# Mainboard_User_Interface.net
KiCad netlist of a schematic drawn in Altium Designer
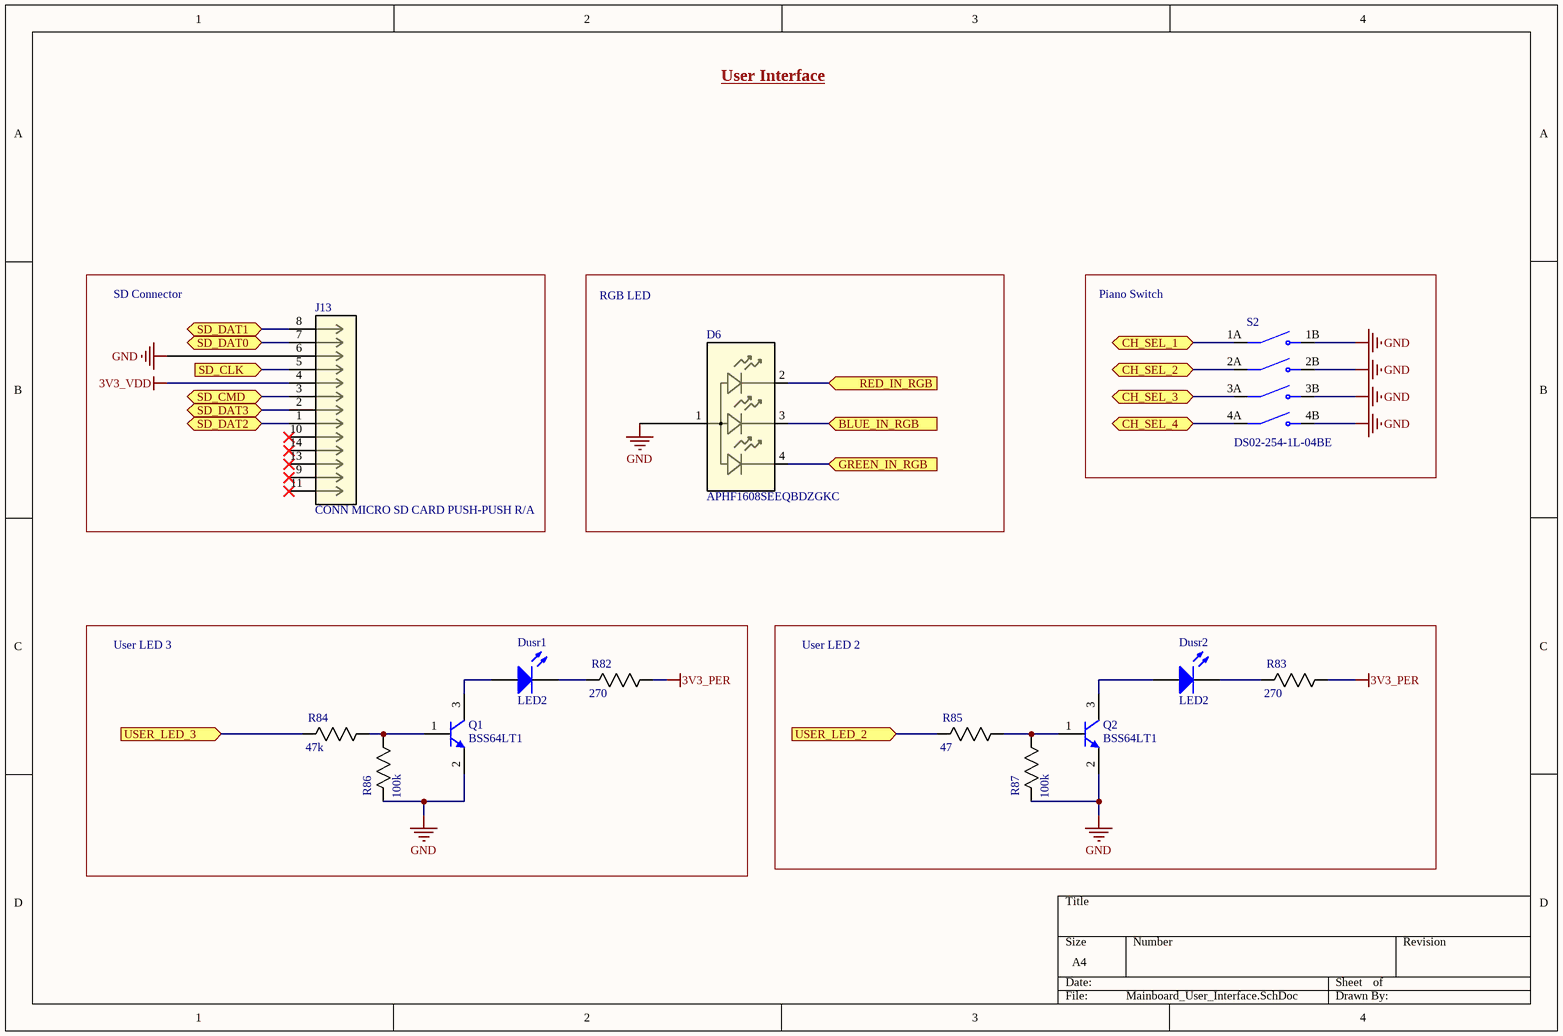
[diagram p0: Mainboard_User_Interface.SchDoc]

(export (version "E")
  (design (tool "Eeschema 10.0.6"))
  (components
    (comp (ref "D6")
      (value "APHF1608SEEQBDZGKC")
      (footprint "LED RGB APHF1608SEEQBDZGKC_KNB-L")
      (fields (field (name "MF") "Kingbright"))
      (libsource (lib "AltiumLibraries") (part "LED RGB CLEAR 4SMD"))
    )
    (comp (ref "Dusr1")
      (value "LED2")
      (footprint "3.2X1.6X1.1")
      (description "Typical RED, GREEN, YELLOW, AMBER GaAs LED")
      (libsource (lib "AltiumLibraries") (part "LED RED SMD"))
    )
    (comp (ref "Dusr2")
      (value "LED2")
      (footprint "3.2X1.6X1.1")
      (description "Typical RED, GREEN, YELLOW, AMBER GaAs LED")
      (libsource (lib "AltiumLibraries") (part "LED GREEN SMD"))
    )
    (comp (ref "J13")
      (value "CONN MICRO SD CARD PUSH-PUSH R/A")
      (footprint "SD Connector 5027740891")
      (description "10 (8 + 2) Position Card Connector Secure Digital - microSD™ Surface Mount, Right Angle Gold")
      (fields (field (name "MF") "Molex") (field (name "MP") "5027740891"))
      (libsource (lib "AltiumLibraries") (part "CONN MICRO SD CARD PUSH-PUSH R/A"))
    )
    (comp (ref "Q1")
      (value "BSS64LT1")
      (footprint "ONSC-SOT-23-3-318-08_V")
      (description "Driver Transistor, NPN Silicon, 3-Pin SOT-23, Tape and Reel")
      (fields (field (name "MANUFACTURER") "On Semiconductor"))
      (libsource (lib "Altium Content Vault") (part "ONSC-NPN-B1E2C3-3"))
    )
    (comp (ref "Q2")
      (value "BSS64LT1")
      (footprint "ONSC-SOT-23-3-318-08_V")
      (description "Driver Transistor, NPN Silicon, 3-Pin SOT-23, Tape and Reel")
      (fields (field (name "MANUFACTURER") "On Semiconductor"))
      (libsource (lib "Altium Content Vault") (part "ONSC-NPN-B1E2C3-3"))
    )
    (comp (ref "R82")
      (value "270")
      (footprint "0805")
      (description "RES SMD 270 OHM 5% 1/8W 0805")
      (fields (field (name "TOLERANCE") "5%"))
      (libsource (lib "AltiumLibraries") (part "RES 270.0 1/8W"))
    )
    (comp (ref "R83")
      (value "270")
      (footprint "0805")
      (description "RES SMD 270 OHM 5% 1/8W 0805")
      (fields (field (name "TOLERANCE") "5%"))
      (libsource (lib "AltiumLibraries") (part "RES 270.0 1/8W"))
    )
    (comp (ref "R84")
      (value "47k")
      (footprint "0805")
      (description "RES SMD 47K OHM 1% 1/8W 0805")
      (fields (field (name "TOLERANCE") "1%"))
      (libsource (lib "AltiumLibraries") (part "RES 47k 1/8W - 1%"))
    )
    (comp (ref "R85")
      (value "47")
      (footprint "0805")
      (description "RES SMD 47 OHM 1% 1/8W 0805")
      (fields (field (name "TOLERANCE") "1%"))
      (libsource (lib "AltiumLibraries") (part "RES 47.0 1/8W - 1%"))
    )
    (comp (ref "R86")
      (value "100k")
      (footprint "0805")
      (description "RES SMD 100K OHM 1% 1/8W 0805")
      (fields (field (name "TOLERANCE") "1%"))
      (libsource (lib "AltiumLibraries") (part "RES 100k 1/8W - 1%"))
    )
    (comp (ref "R87")
      (value "100k")
      (footprint "0805")
      (description "RES SMD 100K OHM 1% 1/8W 0805")
      (fields (field (name "TOLERANCE") "1%"))
      (libsource (lib "AltiumLibraries") (part "RES 100k 1/8W - 1%"))
    )
    (comp (ref "S2")
      (value "DS02-254-1L-04BE")
      (footprint "SW_DS02-254-1L-04BE")
      (description "Dip Switch Piano Key 4-position")
      (libsource (lib "AltiumLibraries") (part "DS02-254-1L-04BE"))
    )
  )
  (nets
    (net (code "1") (name "/BLUE_IN_RGB") (class "Default")
      (node (ref "D6") (pin "3") (pinfunction "3_3") (pintype "passive"))
    )
    (net (code "2") (name "/CH_SEL_1") (class "Default")
      (node (ref "S2") (pin "1A") (pinfunction "COM1_1A") (pintype "passive"))
    )
    (net (code "3") (name "/CH_SEL_2") (class "Default")
      (node (ref "S2") (pin "2A") (pinfunction "COM2_2A") (pintype "passive"))
    )
    (net (code "4") (name "/CH_SEL_3") (class "Default")
      (node (ref "S2") (pin "3A") (pinfunction "COM3_3A") (pintype "passive"))
    )
    (net (code "5") (name "/CH_SEL_4") (class "Default")
      (node (ref "S2") (pin "4A") (pinfunction "COM4_4A") (pintype "passive"))
    )
    (net (code "6") (name "/GREEN_IN_RGB") (class "Default")
      (node (ref "D6") (pin "4") (pinfunction "4_4") (pintype "passive"))
    )
    (net (code "7") (name "/RED_IN_RGB") (class "Default")
      (node (ref "D6") (pin "2") (pinfunction "2_2") (pintype "passive"))
    )
    (net (code "8") (name "/SD_CLK") (class "Default")
      (node (ref "J13") (pin "5") (pinfunction "5_5") (pintype "passive"))
    )
    (net (code "9") (name "/SD_CMD") (class "Default")
      (node (ref "J13") (pin "3") (pinfunction "3_3") (pintype "passive"))
    )
    (net (code "10") (name "/SD_DAT0") (class "Default")
      (node (ref "J13") (pin "7") (pinfunction "7_7") (pintype "passive"))
    )
    (net (code "11") (name "/SD_DAT1") (class "Default")
      (node (ref "J13") (pin "8") (pinfunction "8_8") (pintype "passive"))
    )
    (net (code "12") (name "/SD_DAT2") (class "Default")
      (node (ref "J13") (pin "1") (pinfunction "1_1") (pintype "passive"))
    )
    (net (code "13") (name "/SD_DAT3") (class "Default")
      (node (ref "J13") (pin "2") (pinfunction "2_2") (pintype "passive"))
    )
    (net (code "14") (name "/USER_LED_2") (class "Default")
      (node (ref "R85") (pin "2") (pinfunction "R2_2") (pintype "passive"))
    )
    (net (code "15") (name "/USER_LED_3") (class "Default")
      (node (ref "R84") (pin "2") (pinfunction "R2_2") (pintype "passive"))
    )
    (net (code "16") (name "3V3_PER") (class "Default")
      (node (ref "R82") (pin "1") (pinfunction "R1_1") (pintype "passive"))
      (node (ref "R83") (pin "1") (pinfunction "R1_1") (pintype "passive"))
    )
    (net (code "17") (name "3V3_VDD") (class "Default")
      (node (ref "J13") (pin "4") (pinfunction "4_4") (pintype "passive"))
    )
    (net (code "18") (name "GND") (class "Default")
      (node (ref "D6") (pin "1") (pinfunction "1_1") (pintype "passive"))
      (node (ref "J13") (pin "6") (pinfunction "6_6") (pintype "passive"))
      (node (ref "Q1") (pin "2") (pinfunction "E_2") (pintype "passive"))
      (node (ref "Q2") (pin "2") (pinfunction "E_2") (pintype "passive"))
      (node (ref "R86") (pin "2") (pinfunction "R2_2") (pintype "passive"))
      (node (ref "R87") (pin "2") (pinfunction "R2_2") (pintype "passive"))
      (node (ref "S2") (pin "1B") (pinfunction "NO1_1B") (pintype "passive"))
      (node (ref "S2") (pin "2B") (pinfunction "NO2_2B") (pintype "passive"))
      (node (ref "S2") (pin "3B") (pinfunction "NO3_3B") (pintype "passive"))
      (node (ref "S2") (pin "4B") (pinfunction "NO4_4B") (pintype "passive"))
    )
    (net (code "19") (name "Net-(Dusr1-A)") (class "Default")
      (node (ref "Dusr1") (pin "1") (pinfunction "A_1") (pintype "passive"))
      (node (ref "Q1") (pin "3") (pinfunction "C_3") (pintype "passive"))
    )
    (net (code "20") (name "Net-(Dusr1-K)") (class "Default")
      (node (ref "Dusr1") (pin "2") (pinfunction "K_2") (pintype "passive"))
      (node (ref "R82") (pin "2") (pinfunction "R2_2") (pintype "passive"))
    )
    (net (code "21") (name "Net-(Dusr2-A)") (class "Default")
      (node (ref "Dusr2") (pin "1") (pinfunction "A_1") (pintype "passive"))
      (node (ref "Q2") (pin "3") (pinfunction "C_3") (pintype "passive"))
    )
    (net (code "22") (name "Net-(Dusr2-K)") (class "Default")
      (node (ref "Dusr2") (pin "2") (pinfunction "K_2") (pintype "passive"))
      (node (ref "R83") (pin "2") (pinfunction "R2_2") (pintype "passive"))
    )
    (net (code "23") (name "Net-(Q1-B)") (class "Default")
      (node (ref "Q1") (pin "1") (pinfunction "B_1") (pintype "passive"))
      (node (ref "R84") (pin "1") (pinfunction "R1_1") (pintype "passive"))
      (node (ref "R86") (pin "1") (pinfunction "R1_1") (pintype "passive"))
    )
    (net (code "24") (name "Net-(Q2-B)") (class "Default")
      (node (ref "Q2") (pin "1") (pinfunction "B_1") (pintype "passive"))
      (node (ref "R85") (pin "1") (pinfunction "R1_1") (pintype "passive"))
      (node (ref "R87") (pin "1") (pinfunction "R1_1") (pintype "passive"))
    )
    (net (code "25") (name "unconnected-(J13-Pad9)") (class "Default")
      (node (ref "J13") (pin "9") (pinfunction "9_9") (pintype "passive+no_connect"))
    )
    (net (code "26") (name "unconnected-(J13-Pad10)") (class "Default")
      (node (ref "J13") (pin "10") (pinfunction "10_10") (pintype "passive+no_connect"))
    )
    (net (code "27") (name "unconnected-(J13-Pad11)") (class "Default")
      (node (ref "J13") (pin "11") (pinfunction "11_11") (pintype "passive+no_connect"))
    )
    (net (code "28") (name "unconnected-(J13-Pad13)") (class "Default")
      (node (ref "J13") (pin "13") (pinfunction "13_13") (pintype "passive+no_connect"))
    )
    (net (code "29") (name "unconnected-(J13-Pad14)") (class "Default")
      (node (ref "J13") (pin "14") (pinfunction "14_14") (pintype "passive+no_connect"))
    )
  )
)
